# cereal-sch.net
KiCad netlist of a schematic drawn in Altium Designer
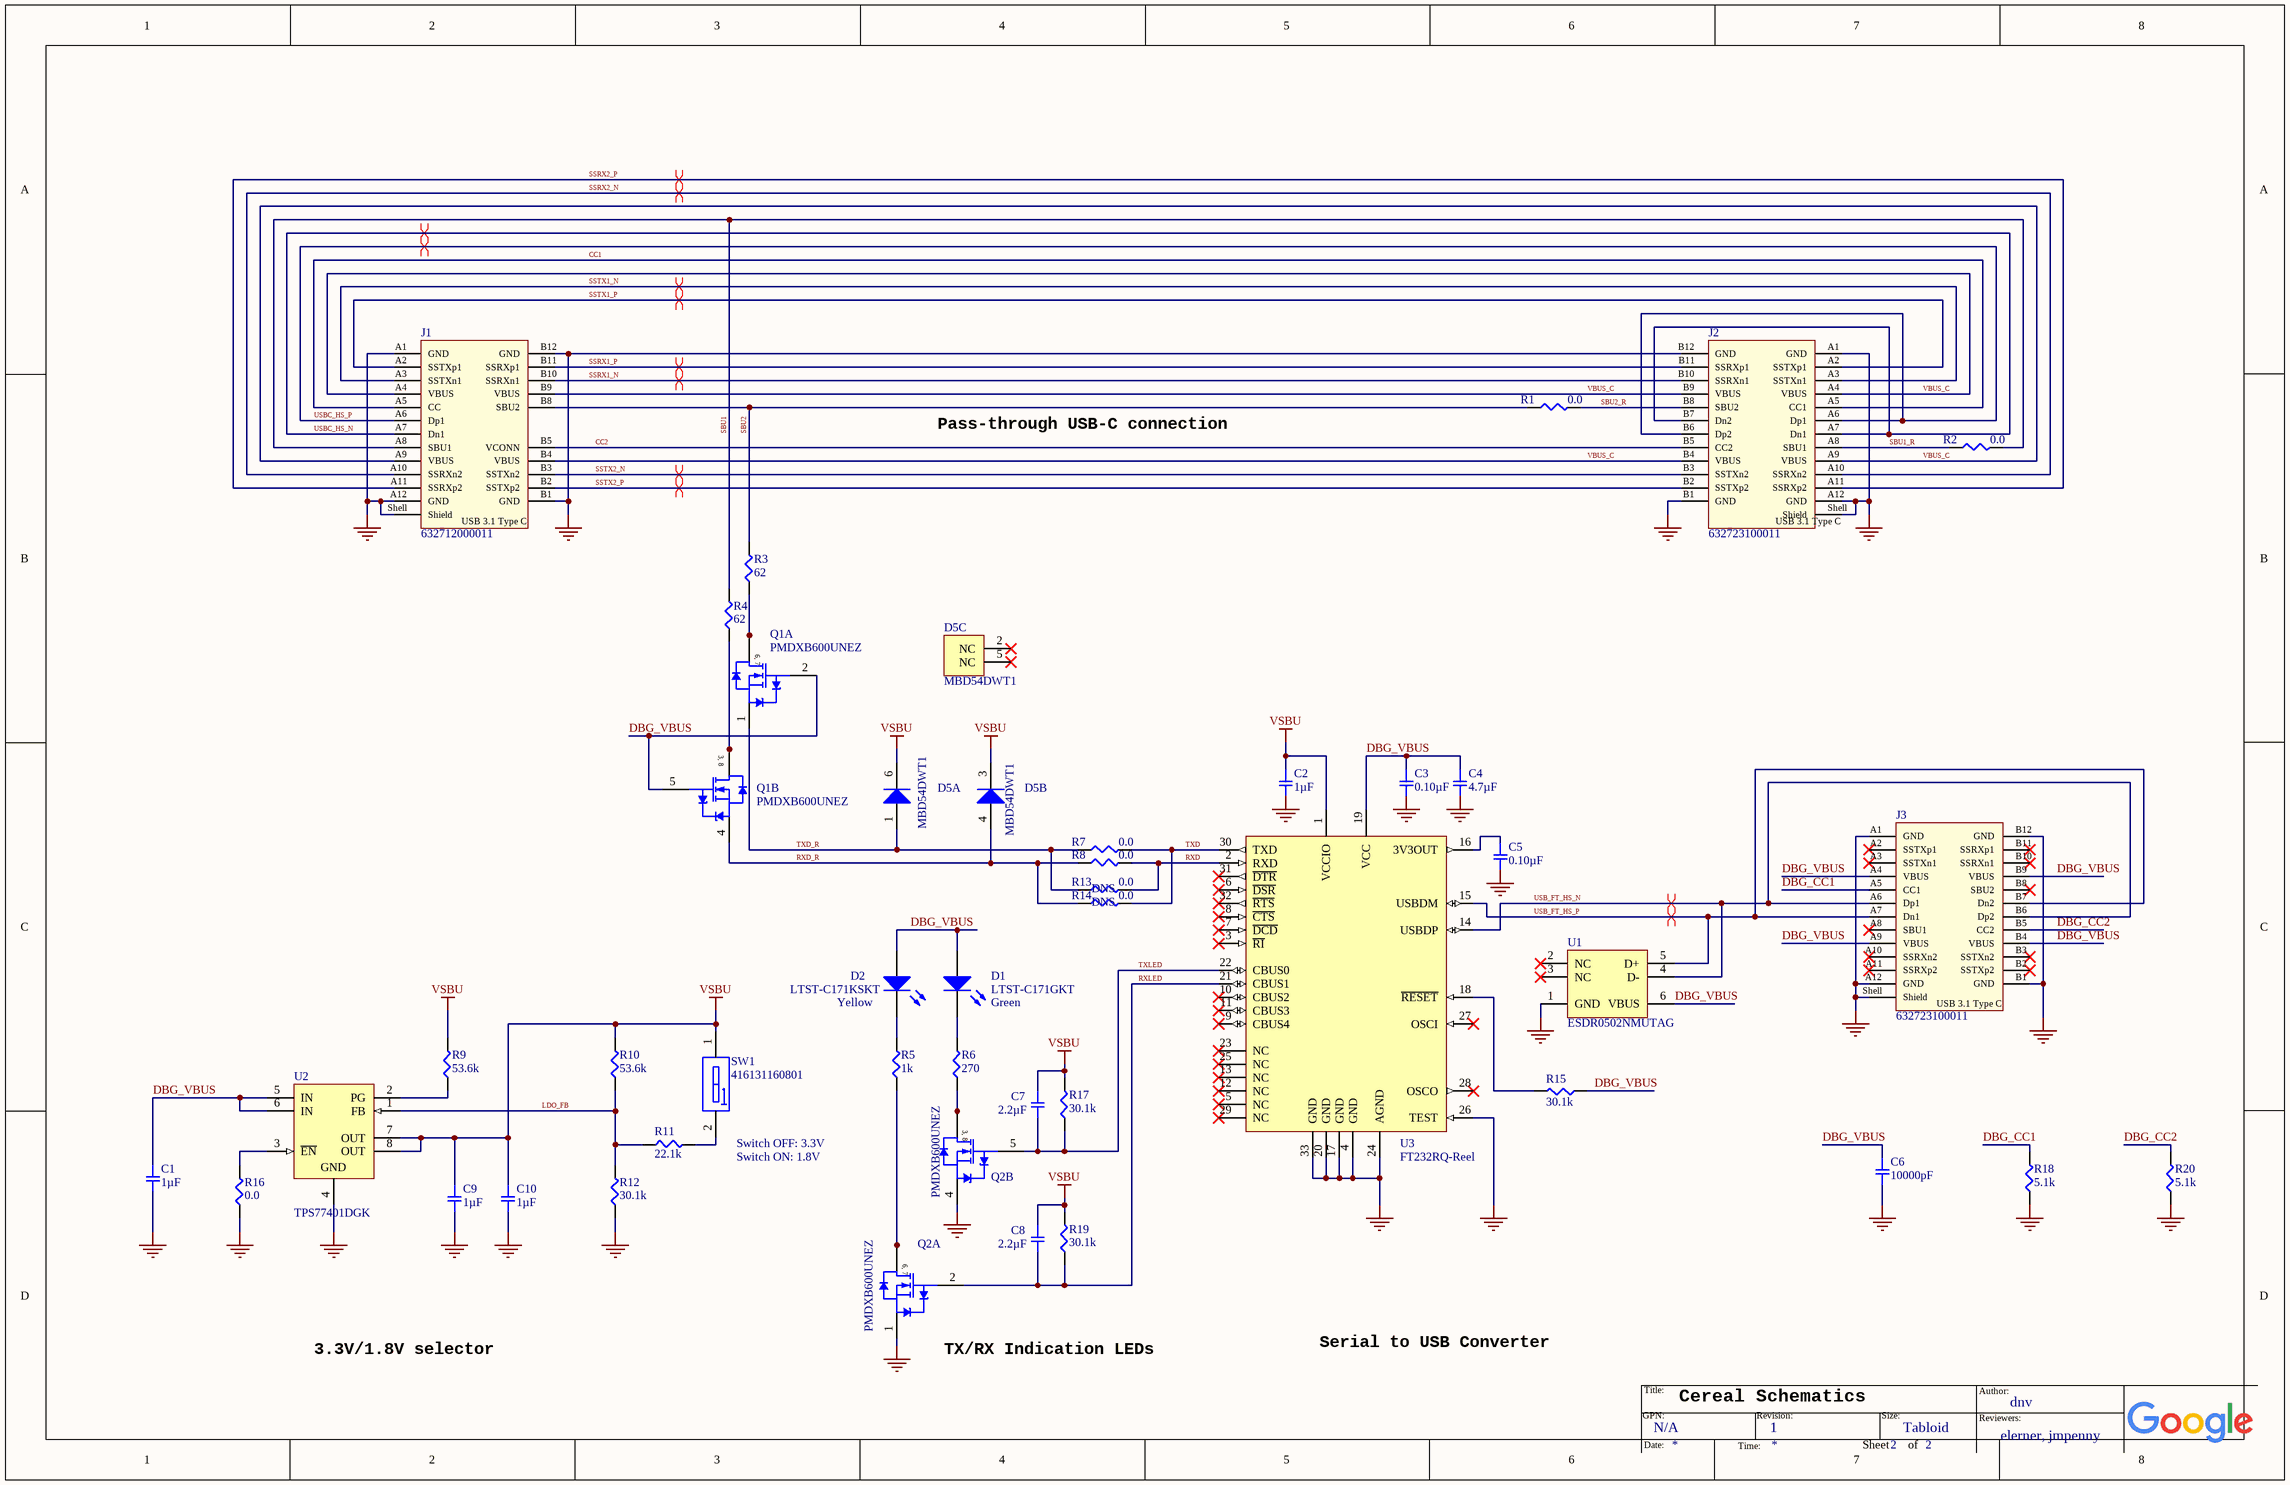
[diagram p0: cereal-sch.SchDoc]

(export (version "E")
  (design (tool "Eeschema 10.0.6"))
  (components
    (comp (ref "C1")
      (value "1µF")
      (footprint "SMD-0201C")
      (description "CAP CER 1UF 6.3V X5R 0201")
      (fields
        (field (name "DIGI-KEY PART NUMBER") "490-7229-1-ND")
        (field (name "PART NUMBER") "GRM033R60J105MEA2D")
      )
      (libsource (lib "capacitor_murata_0201") (part "GRM033R60J105MEA2D"))
    )
    (comp (ref "C2")
      (value "1µF")
      (footprint "SMD-0201C")
      (description "CAP CER 1UF 6.3V X5R 0201")
      (fields
        (field (name "DIGI-KEY PART NUMBER") "490-7229-1-ND")
        (field (name "PART NUMBER") "GRM033R60J105MEA2D")
      )
      (libsource (lib "capacitor_murata_0201") (part "GRM033R60J105MEA2D"))
    )
    (comp (ref "C3")
      (value "0.10µF")
      (footprint "SMD-0201C")
      (description "CAP CER 0.1UF 10V X5R 0201")
      (fields
        (field (name "DIGI-KEY PART NUMBER") "490-5881-1-ND")
        (field (name "PART NUMBER") "GRM033R61A104KE15D")
      )
      (libsource (lib "capacitor_murata_0201") (part "GRM033R61A104KE15D"))
    )
    (comp (ref "C4")
      (value "4.7µF")
      (footprint "SMD-0402C")
      (description "CAP CER 4.7UF 4V X5R 0402")
      (fields
        (field (name "DIGI-KEY PART NUMBER") "490-13231-1-ND")
        (field (name "PART NUMBER") "GRM153R60G475ME15D")
      )
      (libsource (lib "capacitor_murata_0402") (part "GRM153R60G475ME15D"))
    )
    (comp (ref "C5")
      (value "0.10µF")
      (footprint "SMD-0201C")
      (description "CAP CER 0.1UF 10V X5R 0201")
      (fields
        (field (name "DIGI-KEY PART NUMBER") "490-5881-1-ND")
        (field (name "PART NUMBER") "GRM033R61A104KE15D")
      )
      (libsource (lib "capacitor_murata_0201") (part "GRM033R61A104KE15D"))
    )
    (comp (ref "C6")
      (value "10000pF")
      (footprint "SMD-0201C")
      (description "CAP CER 10000PF 10V X5R 0201")
      (fields
        (field (name "DIGI-KEY PART NUMBER") "490-8156-1-ND")
        (field (name "PART NUMBER") "GRM033R61A103KA01J")
      )
      (libsource (lib "capacitor_murata_0201") (part "GRM033R61A103KA01J"))
    )
    (comp (ref "C7")
      (value "2.2µF")
      (footprint "SMD-0201C")
      (description "CAP CER 2.2UF 10V X5R 0201")
      (fields
        (field (name "DIGI-KEY PART NUMBER") "490-13227-1-ND")
        (field (name "PART NUMBER") "GRM033R61A225KE47D")
      )
      (libsource (lib "cap_murata_0201") (part "GRM033R61A225KE47D"))
    )
    (comp (ref "C8")
      (value "2.2µF")
      (footprint "SMD-0201C")
      (description "CAP CER 2.2UF 10V X5R 0201")
      (fields
        (field (name "DIGI-KEY PART NUMBER") "490-13227-1-ND")
        (field (name "PART NUMBER") "GRM033R61A225KE47D")
      )
      (libsource (lib "cap_murata_0201") (part "GRM033R61A225KE47D"))
    )
    (comp (ref "C9")
      (value "1µF")
      (footprint "SMD-0201C")
      (description "CAP CER 1UF 6.3V X5R 0201")
      (fields
        (field (name "DIGI-KEY PART NUMBER") "490-7229-1-ND")
        (field (name "PART NUMBER") "GRM033R60J105MEA2D")
      )
      (libsource (lib "capacitor_murata_0201") (part "GRM033R60J105MEA2D"))
    )
    (comp (ref "C10")
      (value "1µF")
      (footprint "SMD-0201C")
      (description "CAP CER 1UF 6.3V X5R 0201")
      (fields
        (field (name "DIGI-KEY PART NUMBER") "490-7229-1-ND")
        (field (name "PART NUMBER") "GRM033R60J105MEA2D")
      )
      (libsource (lib "capacitor_murata_0201") (part "GRM033R60J105MEA2D"))
    )
    (comp (ref "D1")
      (value "LTST-C171GKT")
      (footprint "0805")
      (description "LED")
      (fields (field (name "COLOR") "Green"))
      (libsource (lib "lite-on") (part "LTST-C171GKT"))
    )
    (comp (ref "D2")
      (value "LTST-C171KSKT")
      (footprint "0805")
      (description "LED")
      (fields (field (name "COLOR") "Yellow"))
      (libsource (lib "lite-on") (part "LTST-C171KSKT"))
    )
    (comp (ref "D5")
      (value "MBD54DWT1")
      (footprint "ONSC-SOT-363-6-419B-02_W_V")
      (description "Dual Schottky Barrier Diodes, 6-Pin SOT-363, Tape and Reel")
      (fields (field (name "MANUFACTURER") "On Semiconductor"))
      (libsource (lib "") (part "MBD54DWT1_1"))
    )
    (comp (ref "J1")
      (value "632712000011")
      (footprint "632712000011")
      (description "USB 3.1 Type C Plug Horizontal SMT WR-COM")
      (fields (field (name "PUBLISHER") "Wurth Elektronik"))
      (libsource (lib "connector_usbc") (part "632712000011"))
    )
    (comp (ref "J2")
      (value "632723100011")
      (footprint "632723100011")
      (description "USB 3.1 Type C Receptacle Horizontal THR WR-COM")
      (fields (field (name "PUBLISHER") "Wurth Elektronik"))
      (libsource (lib "connector_usbc") (part "632723100011"))
    )
    (comp (ref "J3")
      (value "632723100011")
      (footprint "632723100011")
      (description "USB 3.1 Type C Receptacle Horizontal THR WR-COM")
      (fields (field (name "PUBLISHER") "Wurth Elektronik"))
      (libsource (lib "") (part "632723100011_1"))
    )
    (comp (ref "Q1")
      (value "PMDXB600UNEZ")
      (footprint "NXP-SOT1216_N")
      (description "Dual N-Channel Trench MOSFET, 20 V, 0.6 A, -55 to 150 degC, 8-Pin SOT1216")
      (fields (field (name "MANUFACTURER") "NXP Semiconductors"))
      (libsource (lib "transistor_NXP_standard_MOSFETs") (part "PMDXB600UNEZ"))
    )
    (comp (ref "Q2")
      (value "PMDXB600UNEZ")
      (footprint "NXP-SOT1216_N")
      (description "Dual N-Channel Trench MOSFET, 20 V, 0.6 A, -55 to 150 degC, 8-Pin SOT1216")
      (fields (field (name "MANUFACTURER") "NXP Semiconductors"))
      (libsource (lib "transistor_NXP_standard_MOSFETs") (part "PMDXB600UNEZ"))
    )
    (comp (ref "R1")
      (value "0.0")
      (footprint "SMD-0201-RES")
      (description "RES SMD 0.0OHM JUMPER 1/20W 0201")
      (fields (field (name "PART NUMBER") "ERJ-1GN0R00C") (field (name "DIGI-KEY PART NUMBER") "P15979CT-ND"))
      (libsource (lib "resistor_0201_panasonic_ERJ") (part "ERJ-1GN0R00C"))
    )
    (comp (ref "R2")
      (value "0.0")
      (footprint "SMD-0201-RES")
      (description "RES SMD 0.0OHM JUMPER 1/20W 0201")
      (fields (field (name "PART NUMBER") "ERJ-1GN0R00C") (field (name "DIGI-KEY PART NUMBER") "P15979CT-ND"))
      (libsource (lib "resistor_0201_panasonic_ERJ") (part "ERJ-1GN0R00C"))
    )
    (comp (ref "R3")
      (value "62")
      (footprint "SMD-0402-RES")
      (description "RES SMD 62 OHM 5% 1/10W 0402")
      (fields (field (name "PART NUMBER") "ERJ-2GEJ620X") (field (name "DIGI-KEY PART NUMBER") "P62JCT-ND"))
      (libsource (lib "resisitor_0402_panasonic_ERJ") (part "ERJ-2GEJ620X"))
    )
    (comp (ref "R4")
      (value "62")
      (footprint "SMD-0402-RES")
      (description "RES SMD 62 OHM 5% 1/10W 0402")
      (fields (field (name "PART NUMBER") "ERJ-2GEJ620X") (field (name "DIGI-KEY PART NUMBER") "P62JCT-ND"))
      (libsource (lib "resisitor_0402_panasonic_ERJ") (part "ERJ-2GEJ620X"))
    )
    (comp (ref "R5")
      (value "1k")
      (footprint "SMD-0201-RES")
      (description "RES SMD 1K OHM 1% 1/20W 0201")
      (fields
        (field (name "PART NUMBER") "ERJ-1GEF1001C")
        (field (name "DIGI-KEY PART NUMBER") "P1.00KABCT-ND")
      )
      (libsource (lib "res_0201_panasonic_ERJ") (part "ERJ-1GEF1001C"))
    )
    (comp (ref "R6")
      (value "270")
      (footprint "SMD-0201-RES")
      (description "RES SMD 270 OHM 1% 1/20W 0201")
      (fields
        (field (name "PART NUMBER") "ERJ-1GEF2700C")
        (field (name "DIGI-KEY PART NUMBER") "P270ABCT-ND")
      )
      (libsource (lib "resistor_0201_panasonic_ERJ") (part "ERJ-1GEF2700C"))
    )
    (comp (ref "R7")
      (value "0.0")
      (footprint "SMD-0201-RES")
      (description "RES SMD 0.0OHM JUMPER 1/20W 0201")
      (fields (field (name "PART NUMBER") "ERJ-1GN0R00C") (field (name "DIGI-KEY PART NUMBER") "P15979CT-ND"))
      (libsource (lib "resistor_0201_panasonic_ERJ") (part "ERJ-1GN0R00C"))
    )
    (comp (ref "R8")
      (value "0.0")
      (footprint "SMD-0201-RES")
      (description "RES SMD 0.0OHM JUMPER 1/20W 0201")
      (fields (field (name "PART NUMBER") "ERJ-1GN0R00C") (field (name "DIGI-KEY PART NUMBER") "P15979CT-ND"))
      (libsource (lib "resistor_0201_panasonic_ERJ") (part "ERJ-1GN0R00C"))
    )
    (comp (ref "R9")
      (value "53.6k")
      (footprint "SMD-0201-RES")
      (description "RES SMD 53.6K OHM 1% 1/20W 0201")
      (fields
        (field (name "PART NUMBER") "ERJ-1GEF5362C")
        (field (name "DIGI-KEY PART NUMBER") "P53.6KABCT-ND")
      )
      (libsource (lib "resistor_0201_panasonic_ERJ") (part "ERJ-1GEF5362C"))
    )
    (comp (ref "R10")
      (value "53.6k")
      (footprint "SMD-0201-RES")
      (description "RES SMD 53.6K OHM 1% 1/20W 0201")
      (fields
        (field (name "PART NUMBER") "ERJ-1GEF5362C")
        (field (name "DIGI-KEY PART NUMBER") "P53.6KABCT-ND")
      )
      (libsource (lib "resistor_0201_panasonic_ERJ") (part "ERJ-1GEF5362C"))
    )
    (comp (ref "R11")
      (value "22.1k")
      (footprint "SMD-0201-RES")
      (description "RES SMD 22.1K OHM 1% 1/20W 0201")
      (fields
        (field (name "PART NUMBER") "ERJ-1GEF2212C")
        (field (name "DIGI-KEY PART NUMBER") "P22.1KABCT-ND")
      )
      (libsource (lib "resistor_0201_panasonic_ERJ") (part "ERJ-1GEF2212C"))
    )
    (comp (ref "R12")
      (value "30.1k")
      (footprint "SMD-0201-RES")
      (description "RES SMD 30.1K OHM 1% 1/20W 0201")
      (fields
        (field (name "PART NUMBER") "ERJ-1GEF3012C")
        (field (name "DIGI-KEY PART NUMBER") "P30.1KABCT-ND")
      )
      (libsource (lib "resistor_0201_panasonic_ERJ") (part "ERJ-1GEF3012C"))
    )
    (comp (ref "R13")
      (value "0.0")
      (footprint "SMD-0201-RES")
      (description "RES SMD 0.0OHM JUMPER 1/20W 0201")
      (fields
        (field (name "PART NUMBER") "ERJ-1GN0R00C")
        (field (name "DIGI-KEY PART NUMBER") "P15979CT-ND")
        (field (name "POPULATE") "DNS")
      )
      (libsource (lib "resistor_0201_panasonic_ERJ") (part "ERJ-1GN0R00C"))
    )
    (comp (ref "R14")
      (value "0.0")
      (footprint "SMD-0201-RES")
      (description "RES SMD 0.0OHM JUMPER 1/20W 0201")
      (fields
        (field (name "PART NUMBER") "ERJ-1GN0R00C")
        (field (name "DIGI-KEY PART NUMBER") "P15979CT-ND")
        (field (name "POPULATE") "DNS")
      )
      (libsource (lib "resistor_0201_panasonic_ERJ") (part "ERJ-1GN0R00C"))
    )
    (comp (ref "R15")
      (value "30.1k")
      (footprint "SMD-0201-RES")
      (description "RES SMD 30.1K OHM 1% 1/20W 0201")
      (fields
        (field (name "PART NUMBER") "ERJ-1GEF3012C")
        (field (name "DIGI-KEY PART NUMBER") "P30.1KABCT-ND")
      )
      (libsource (lib "resistor_0201_panasonic_ERJ") (part "ERJ-1GEF3012C"))
    )
    (comp (ref "R16")
      (value "0.0")
      (footprint "SMD-0201-RES")
      (description "RES SMD 0.0OHM JUMPER 1/20W 0201")
      (fields (field (name "PART NUMBER") "ERJ-1GN0R00C") (field (name "DIGI-KEY PART NUMBER") "P15979CT-ND"))
      (libsource (lib "resistor_0201_panasonic_ERJ") (part "ERJ-1GN0R00C"))
    )
    (comp (ref "R17")
      (value "30.1k")
      (footprint "SMD-0201-RES")
      (description "RES SMD 30.1K OHM 1% 1/20W 0201")
      (fields
        (field (name "PART NUMBER") "ERJ-1GEF3012C")
        (field (name "DIGI-KEY PART NUMBER") "P30.1KABCT-ND")
      )
      (libsource (lib "resistor_0201_panasonic_ERJ") (part "ERJ-1GEF3012C"))
    )
    (comp (ref "R18")
      (value "5.1k")
      (footprint "SMD-0201-RES")
      (description "RES SMD 5.1K OHM 1% 1/20W 0201")
      (fields
        (field (name "PART NUMBER") "ERJ-1GEF5101C")
        (field (name "DIGI-KEY PART NUMBER") "P5.10KABCT-ND")
      )
      (libsource (lib "resistor_0201_panasonic_ERJ") (part "ERJ-1GEF5101C"))
    )
    (comp (ref "R19")
      (value "30.1k")
      (footprint "SMD-0201-RES")
      (description "RES SMD 30.1K OHM 1% 1/20W 0201")
      (fields
        (field (name "PART NUMBER") "ERJ-1GEF3012C")
        (field (name "DIGI-KEY PART NUMBER") "P30.1KABCT-ND")
      )
      (libsource (lib "resistor_0201_panasonic_ERJ") (part "ERJ-1GEF3012C"))
    )
    (comp (ref "R20")
      (value "5.1k")
      (footprint "SMD-0201-RES")
      (description "RES SMD 5.1K OHM 1% 1/20W 0201")
      (fields
        (field (name "PART NUMBER") "ERJ-1GEF5101C")
        (field (name "DIGI-KEY PART NUMBER") "P5.10KABCT-ND")
      )
      (libsource (lib "resistor_0201_panasonic_ERJ") (part "ERJ-1GEF5101C"))
    )
    (comp (ref "SW1")
      (value "416131160801")
      (footprint "416131160801")
      (description "WS-DISV 1.27 mm small compact SMD Dip Switch with top tape")
      (libsource (lib "WS-DISV 1.27 mm small compact SMD Dip Switch with top tape") (part "416131160801"))
    )
    (comp (ref "U1")
      (value "ESDR0502NMUTAG")
      (footprint "ONSC-UDFN-6-517AA-01_V")
      (fields (field (name "MANUFACTURER") "On Semiconductor"))
      (libsource (lib "diode_esd_ON_Semi") (part "ESDR0502NMUTAG"))
    )
    (comp (ref "U2")
      (value "TPS77401DGK")
      (footprint "TI-DGK8_N")
      (fields (field (name "MANUFACTURER") "Texas Instruments"))
      (libsource (lib "ic_pwr_ldo_TI_single_channel_ldo_0-350mA") (part "TPS77401DGK"))
    )
    (comp (ref "U3")
      (value "FT232RQ-Reel")
      (footprint "PQFN5X5-32_V")
      (description "USB UART Asynchronous Serial Data Transfer Chip, 32-pin QFN, Tape and Reel")
      (fields (field (name "MANUFACTURER") "FTDI"))
      (libsource (lib "ic_interface_FTDI") (part "FT232RQ-Reel"))
    )
  )
  (nets
    (net (code "1") (name "/CC1") (class "Default")
      (node (ref "J1") (pin "A5") (pinfunction "CC_A5") (pintype "passive"))
      (node (ref "J2") (pin "A5") (pinfunction "CC1_A5") (pintype "passive"))
    )
    (net (code "2") (name "/CC2") (class "Default")
      (node (ref "J1") (pin "B5") (pinfunction "VCONN_B5") (pintype "passive"))
      (node (ref "J2") (pin "B5") (pinfunction "CC2_B5") (pintype "passive"))
    )
    (net (code "3") (name "/DBG_CC1") (class "Default")
      (node (ref "J3") (pin "A5") (pinfunction "CC1_A5") (pintype "passive"))
      (node (ref "R18") (pin "2") (pinfunction "2_2") (pintype "passive"))
    )
    (net (code "4") (name "/DBG_CC2") (class "Default")
      (node (ref "J3") (pin "B5") (pinfunction "CC2_B5") (pintype "passive"))
      (node (ref "R20") (pin "2") (pinfunction "2_2") (pintype "passive"))
    )
    (net (code "5") (name "/DBG_VBUS") (class "Default")
      (node (ref "C1") (pin "1") (pinfunction "1_1") (pintype "passive"))
      (node (ref "C3") (pin "1") (pinfunction "1_1") (pintype "passive"))
      (node (ref "C4") (pin "1") (pinfunction "1_1") (pintype "passive"))
      (node (ref "C6") (pin "1") (pinfunction "1_1") (pintype "passive"))
      (node (ref "D1") (pin "1") (pinfunction "A_1") (pintype "passive"))
      (node (ref "D2") (pin "1") (pinfunction "A_1") (pintype "passive"))
      (node (ref "J3") (pin "A4") (pinfunction "VBUS_A4") (pintype "passive"))
      (node (ref "J3") (pin "A9") (pinfunction "VBUS_A9") (pintype "passive"))
      (node (ref "J3") (pin "B4") (pinfunction "VBUS_B4") (pintype "passive"))
      (node (ref "J3") (pin "B9") (pinfunction "VBUS_B9") (pintype "passive"))
      (node (ref "Q1") (pin "2") (pinfunction "G1_2") (pintype "passive"))
      (node (ref "Q1") (pin "5") (pinfunction "G2_5") (pintype "passive"))
      (node (ref "R15") (pin "1") (pinfunction "1_1") (pintype "passive"))
      (node (ref "U1") (pin "6") (pinfunction "VBUS_6") (pintype "power_in"))
      (node (ref "U2") (pin "5") (pinfunction "IN_5") (pintype "power_in"))
      (node (ref "U2") (pin "6") (pinfunction "IN_6") (pintype "power_in"))
      (node (ref "U3") (pin "19") (pinfunction "VCC_19") (pintype "power_in"))
    )
    (net (code "6") (name "/LDO_FB") (class "Default")
      (node (ref "R10") (pin "1") (pinfunction "1_1") (pintype "passive"))
      (node (ref "R11") (pin "1") (pinfunction "1_1") (pintype "passive"))
      (node (ref "R12") (pin "2") (pinfunction "2_2") (pintype "passive"))
      (node (ref "U2") (pin "1") (pinfunction "FB_1") (pintype "input"))
    )
    (net (code "7") (name "/RXD") (class "Default")
      (node (ref "R13") (pin "2") (pinfunction "2_2") (pintype "passive"))
      (node (ref "R8") (pin "2") (pinfunction "2_2") (pintype "passive"))
      (node (ref "U3") (pin "2") (pinfunction "RXD_2") (pintype "input"))
    )
    (net (code "8") (name "/RXD_R") (class "Default")
      (node (ref "D5") (pin "4") (pinfunction "A1_4") (pintype "passive"))
      (node (ref "Q1") (pin "4") (pinfunction "S2_4") (pintype "passive"))
      (node (ref "R14") (pin "1") (pinfunction "1_1") (pintype "passive"))
      (node (ref "R8") (pin "1") (pinfunction "1_1") (pintype "passive"))
    )
    (net (code "9") (name "/RXLED") (class "Default")
      (node (ref "C8") (pin "2") (pinfunction "2_2") (pintype "passive"))
      (node (ref "Q2") (pin "2") (pinfunction "G1_2") (pintype "passive"))
      (node (ref "R19") (pin "1") (pinfunction "1_1") (pintype "passive"))
      (node (ref "U3") (pin "21") (pinfunction "CBUS1_21") (pintype "bidirectional"))
    )
    (net (code "10") (name "/SBU1") (class "Default")
      (node (ref "J1") (pin "A8") (pinfunction "SBU1_A8") (pintype "passive"))
      (node (ref "R2") (pin "2") (pinfunction "2_2") (pintype "passive"))
      (node (ref "R4") (pin "2") (pinfunction "2_2") (pintype "passive"))
    )
    (net (code "11") (name "/SBU1_R") (class "Default")
      (node (ref "J2") (pin "A8") (pinfunction "SBU1_A8") (pintype "passive"))
      (node (ref "R2") (pin "1") (pinfunction "1_1") (pintype "passive"))
    )
    (net (code "12") (name "/SBU2") (class "Default")
      (node (ref "J1") (pin "B8") (pinfunction "SBU2_B8") (pintype "passive"))
      (node (ref "R1") (pin "1") (pinfunction "1_1") (pintype "passive"))
      (node (ref "R3") (pin "2") (pinfunction "2_2") (pintype "passive"))
    )
    (net (code "13") (name "/SBU2_R") (class "Default")
      (node (ref "J2") (pin "B8") (pinfunction "SBU2_B8") (pintype "passive"))
      (node (ref "R1") (pin "2") (pinfunction "2_2") (pintype "passive"))
    )
    (net (code "14") (name "/SSRX1_N") (class "Default")
      (node (ref "J1") (pin "B10") (pinfunction "SSRXn1_B10") (pintype "passive"))
      (node (ref "J2") (pin "B10") (pinfunction "SSRXn1_B10") (pintype "passive"))
    )
    (net (code "15") (name "/SSRX1_P") (class "Default")
      (node (ref "J1") (pin "B11") (pinfunction "SSRXp1_B11") (pintype "passive"))
      (node (ref "J2") (pin "B11") (pinfunction "SSRXp1_B11") (pintype "passive"))
    )
    (net (code "16") (name "/SSRX2_N") (class "Default")
      (node (ref "J1") (pin "A10") (pinfunction "SSRXn2_A10") (pintype "passive"))
      (node (ref "J2") (pin "A10") (pinfunction "SSRXn2_A10") (pintype "passive"))
    )
    (net (code "17") (name "/SSRX2_P") (class "Default")
      (node (ref "J1") (pin "A11") (pinfunction "SSRXp2_A11") (pintype "passive"))
      (node (ref "J2") (pin "A11") (pinfunction "SSRXp2_A11") (pintype "passive"))
    )
    (net (code "18") (name "/SSTX1_N") (class "Default")
      (node (ref "J1") (pin "A3") (pinfunction "SSTXn1_A3") (pintype "passive"))
      (node (ref "J2") (pin "A3") (pinfunction "SSTXn1_A3") (pintype "passive"))
    )
    (net (code "19") (name "/SSTX1_P") (class "Default")
      (node (ref "J1") (pin "A2") (pinfunction "SSTXp1_A2") (pintype "passive"))
      (node (ref "J2") (pin "A2") (pinfunction "SSTXp1_A2") (pintype "passive"))
    )
    (net (code "20") (name "/SSTX2_N") (class "Default")
      (node (ref "J1") (pin "B3") (pinfunction "SSTXn2_B3") (pintype "passive"))
      (node (ref "J2") (pin "B3") (pinfunction "SSTXn2_B3") (pintype "passive"))
    )
    (net (code "21") (name "/SSTX2_P") (class "Default")
      (node (ref "J1") (pin "B2") (pinfunction "SSTXp2_B2") (pintype "passive"))
      (node (ref "J2") (pin "B2") (pinfunction "SSTXp2_B2") (pintype "passive"))
    )
    (net (code "22") (name "/TXD") (class "Default")
      (node (ref "R14") (pin "2") (pinfunction "2_2") (pintype "passive"))
      (node (ref "R7") (pin "2") (pinfunction "2_2") (pintype "passive"))
      (node (ref "U3") (pin "30") (pinfunction "TXD_30") (pintype "output"))
    )
    (net (code "23") (name "/TXD_R") (class "Default")
      (node (ref "D5") (pin "1") (pinfunction "A2_1") (pintype "passive"))
      (node (ref "Q1") (pin "1") (pinfunction "S1_1") (pintype "passive"))
      (node (ref "R13") (pin "1") (pinfunction "1_1") (pintype "passive"))
      (node (ref "R7") (pin "1") (pinfunction "1_1") (pintype "passive"))
    )
    (net (code "24") (name "/TXLED") (class "Default")
      (node (ref "C7") (pin "2") (pinfunction "2_2") (pintype "passive"))
      (node (ref "Q2") (pin "5") (pinfunction "G2_5") (pintype "passive"))
      (node (ref "R17") (pin "1") (pinfunction "1_1") (pintype "passive"))
      (node (ref "U3") (pin "22") (pinfunction "CBUS0_22") (pintype "bidirectional"))
    )
    (net (code "25") (name "/USBC_HS_N") (class "Default")
      (node (ref "J1") (pin "A7") (pinfunction "Dn1_A7") (pintype "passive"))
      (node (ref "J2") (pin "A7") (pinfunction "Dn1_A7") (pintype "passive"))
      (node (ref "J2") (pin "B7") (pinfunction "Dn2_B7") (pintype "passive"))
    )
    (net (code "26") (name "/USBC_HS_P") (class "Default")
      (node (ref "J1") (pin "A6") (pinfunction "Dp1_A6") (pintype "passive"))
      (node (ref "J2") (pin "A6") (pinfunction "Dp1_A6") (pintype "passive"))
      (node (ref "J2") (pin "B6") (pinfunction "Dp2_B6") (pintype "passive"))
    )
    (net (code "27") (name "/USB_FT_HS_N") (class "Default")
      (node (ref "J3") (pin "A6") (pinfunction "Dp1_A6") (pintype "passive"))
      (node (ref "J3") (pin "B6") (pinfunction "Dp2_B6") (pintype "passive"))
      (node (ref "U1") (pin "4") (pinfunction "D-_4") (pintype "passive"))
      (node (ref "U3") (pin "14") (pinfunction "USBDP_14") (pintype "bidirectional"))
    )
    (net (code "28") (name "/USB_FT_HS_P") (class "Default")
      (node (ref "J3") (pin "A7") (pinfunction "Dn1_A7") (pintype "passive"))
      (node (ref "J3") (pin "B7") (pinfunction "Dn2_B7") (pintype "passive"))
      (node (ref "U1") (pin "5") (pinfunction "D+_5") (pintype "passive"))
      (node (ref "U3") (pin "15") (pinfunction "USBDM_15") (pintype "bidirectional"))
    )
    (net (code "29") (name "/VBUS_C") (class "Default")
      (node (ref "J1") (pin "A4") (pinfunction "VBUS_A4") (pintype "passive"))
      (node (ref "J1") (pin "A9") (pinfunction "VBUS_A9") (pintype "passive"))
      (node (ref "J1") (pin "B4") (pinfunction "VBUS_B4") (pintype "passive"))
      (node (ref "J1") (pin "B9") (pinfunction "VBUS_B9") (pintype "passive"))
      (node (ref "J2") (pin "A4") (pinfunction "VBUS_A4") (pintype "passive"))
      (node (ref "J2") (pin "A9") (pinfunction "VBUS_A9") (pintype "passive"))
      (node (ref "J2") (pin "B4") (pinfunction "VBUS_B4") (pintype "passive"))
      (node (ref "J2") (pin "B9") (pinfunction "VBUS_B9") (pintype "passive"))
    )
    (net (code "30") (name "GND") (class "Default")
      (node (ref "C1") (pin "2") (pinfunction "2_2") (pintype "passive"))
      (node (ref "C10") (pin "2") (pinfunction "2_2") (pintype "passive"))
      (node (ref "C2") (pin "2") (pinfunction "2_2") (pintype "passive"))
      (node (ref "C3") (pin "2") (pinfunction "2_2") (pintype "passive"))
      (node (ref "C4") (pin "2") (pinfunction "2_2") (pintype "passive"))
      (node (ref "C5") (pin "2") (pinfunction "2_2") (pintype "passive"))
      (node (ref "C6") (pin "2") (pinfunction "2_2") (pintype "passive"))
      (node (ref "C9") (pin "2") (pinfunction "2_2") (pintype "passive"))
      (node (ref "J1") (pin "A1") (pinfunction "GND_A1") (pintype "passive"))
      (node (ref "J1") (pin "A12") (pinfunction "GND_A12") (pintype "passive"))
      (node (ref "J1") (pin "B1") (pinfunction "GND_B1") (pintype "passive"))
      (node (ref "J1") (pin "B12") (pinfunction "GND_B12") (pintype "passive"))
      (node (ref "J1") (pin "Shell") (pinfunction "Shield_Shell") (pintype "passive"))
      (node (ref "J2") (pin "A1") (pinfunction "GND_A1") (pintype "passive"))
      (node (ref "J2") (pin "A12") (pinfunction "GND_A12") (pintype "passive"))
      (node (ref "J2") (pin "B1") (pinfunction "GND_B1") (pintype "passive"))
      (node (ref "J2") (pin "B12") (pinfunction "GND_B12") (pintype "passive"))
      (node (ref "J2") (pin "Shell") (pinfunction "Shield_Shell") (pintype "passive"))
      (node (ref "J3") (pin "A1") (pinfunction "GND_A1") (pintype "passive"))
      (node (ref "J3") (pin "A12") (pinfunction "GND_A12") (pintype "passive"))
      (node (ref "J3") (pin "B1") (pinfunction "GND_B1") (pintype "passive"))
      (node (ref "J3") (pin "B12") (pinfunction "GND_B12") (pintype "passive"))
      (node (ref "J3") (pin "Shell") (pinfunction "Shield_Shell") (pintype "passive"))
      (node (ref "Q2") (pin "1") (pinfunction "S1_1") (pintype "passive"))
      (node (ref "Q2") (pin "4") (pinfunction "S2_4") (pintype "passive"))
      (node (ref "R12") (pin "1") (pinfunction "1_1") (pintype "passive"))
      (node (ref "R16") (pin "1") (pinfunction "1_1") (pintype "passive"))
      (node (ref "R18") (pin "1") (pinfunction "1_1") (pintype "passive"))
      (node (ref "R20") (pin "1") (pinfunction "1_1") (pintype "passive"))
      (node (ref "U1") (pin "1") (pinfunction "GND_1") (pintype "power_in"))
      (node (ref "U2") (pin "4") (pinfunction "GND_4") (pintype "power_in"))
      (node (ref "U3") (pin "17") (pinfunction "GND_17") (pintype "power_in"))
      (node (ref "U3") (pin "20") (pinfunction "GND_20") (pintype "power_in"))
      (node (ref "U3") (pin "24") (pinfunction "AGND_24") (pintype "power_in"))
      (node (ref "U3") (pin "26") (pinfunction "TEST_26") (pintype "input"))
      (node (ref "U3") (pin "33") (pinfunction "GND_33") (pintype "power_in"))
      (node (ref "U3") (pin "4") (pinfunction "GND_4") (pintype "power_in"))
    )
    (net (code "31") (name "Net-(D1-K)") (class "Default")
      (node (ref "D1") (pin "2") (pinfunction "K_2") (pintype "passive"))
      (node (ref "R6") (pin "2") (pinfunction "2_2") (pintype "passive"))
    )
    (net (code "32") (name "Net-(D2-K)") (class "Default")
      (node (ref "D2") (pin "2") (pinfunction "K_2") (pintype "passive"))
      (node (ref "R5") (pin "2") (pinfunction "2_2") (pintype "passive"))
    )
    (net (code "33") (name "Net-(Q1A-D1-Pad6)") (class "Default")
      (node (ref "Q1") (pin "6") (pinfunction "D1_6") (pintype "passive"))
      (node (ref "Q1") (pin "7") (pinfunction "D1_7") (pintype "passive"))
      (node (ref "R3") (pin "1") (pinfunction "1_1") (pintype "passive"))
    )
    (net (code "34") (name "Net-(Q1B-D2-Pad3)") (class "Default")
      (node (ref "Q1") (pin "3") (pinfunction "D2_3") (pintype "passive"))
      (node (ref "Q1") (pin "8") (pinfunction "D2_8") (pintype "passive"))
      (node (ref "R4") (pin "1") (pinfunction "1_1") (pintype "passive"))
    )
    (net (code "35") (name "Net-(Q2A-D1-Pad6)") (class "Default")
      (node (ref "Q2") (pin "6") (pinfunction "D1_6") (pintype "passive"))
      (node (ref "Q2") (pin "7") (pinfunction "D1_7") (pintype "passive"))
      (node (ref "R5") (pin "1") (pinfunction "1_1") (pintype "passive"))
    )
    (net (code "36") (name "Net-(Q2B-D2-Pad3)") (class "Default")
      (node (ref "Q2") (pin "3") (pinfunction "D2_3") (pintype "passive"))
      (node (ref "Q2") (pin "8") (pinfunction "D2_8") (pintype "passive"))
      (node (ref "R6") (pin "1") (pinfunction "1_1") (pintype "passive"))
    )
    (net (code "37") (name "Net-(R11-Pad2)") (class "Default")
      (node (ref "R11") (pin "2") (pinfunction "2_2") (pintype "passive"))
      (node (ref "SW1") (pin "2") (pinfunction "2_2") (pintype "passive"))
    )
    (net (code "38") (name "Net-(U2-PG)") (class "Default")
      (node (ref "R9") (pin "1") (pinfunction "1_1") (pintype "passive"))
      (node (ref "U2") (pin "2") (pinfunction "PG_2") (pintype "tri_state"))
    )
    (net (code "39") (name "Net-(U2-~{EN})") (class "Default")
      (node (ref "R16") (pin "2") (pinfunction "2_2") (pintype "passive"))
      (node (ref "U2") (pin "3") (pinfunction "~{EN}_3") (pintype "input"))
    )
    (net (code "40") (name "Net-(U3-3V3OUT)") (class "Default")
      (node (ref "C5") (pin "1") (pinfunction "1_1") (pintype "passive"))
      (node (ref "U3") (pin "16") (pinfunction "3V3OUT_16") (pintype "output"))
    )
    (net (code "41") (name "Net-(U3-~{RESET})") (class "Default")
      (node (ref "R15") (pin "2") (pinfunction "2_2") (pintype "passive"))
      (node (ref "U3") (pin "18") (pinfunction "~{RESET}_18") (pintype "input"))
    )
    (net (code "42") (name "VSBU") (class "Default")
      (node (ref "C10") (pin "1") (pinfunction "1_1") (pintype "passive"))
      (node (ref "C2") (pin "1") (pinfunction "1_1") (pintype "passive"))
      (node (ref "C7") (pin "1") (pinfunction "1_1") (pintype "passive"))
      (node (ref "C8") (pin "1") (pinfunction "1_1") (pintype "passive"))
      (node (ref "C9") (pin "1") (pinfunction "1_1") (pintype "passive"))
      (node (ref "D5") (pin "3") (pinfunction "K1_3") (pintype "passive"))
      (node (ref "D5") (pin "6") (pinfunction "K2_6") (pintype "passive"))
      (node (ref "R10") (pin "2") (pinfunction "2_2") (pintype "passive"))
      (node (ref "R17") (pin "2") (pinfunction "2_2") (pintype "passive"))
      (node (ref "R19") (pin "2") (pinfunction "2_2") (pintype "passive"))
      (node (ref "R9") (pin "2") (pinfunction "2_2") (pintype "passive"))
      (node (ref "SW1") (pin "1") (pinfunction "1_1") (pintype "passive"))
      (node (ref "U2") (pin "7") (pinfunction "OUT_7") (pintype "power_in"))
      (node (ref "U2") (pin "8") (pinfunction "OUT_8") (pintype "power_in"))
      (node (ref "U3") (pin "1") (pinfunction "VCCIO_1") (pintype "power_in"))
    )
    (net (code "43") (name "unconnected-(D5C-NC-Pad2)") (class "Default")
      (node (ref "D5") (pin "2") (pinfunction "NC_2") (pintype "passive+no_connect"))
    )
    (net (code "44") (name "unconnected-(D5C-NC-Pad5)") (class "Default")
      (node (ref "D5") (pin "5") (pinfunction "NC_5") (pintype "passive+no_connect"))
    )
    (net (code "45") (name "unconnected-(J3-SBU1-PadA8)") (class "Default")
      (node (ref "J3") (pin "A8") (pinfunction "SBU1_A8") (pintype "passive+no_connect"))
    )
    (net (code "46") (name "unconnected-(J3-SBU2-PadB8)") (class "Default")
      (node (ref "J3") (pin "B8") (pinfunction "SBU2_B8") (pintype "passive+no_connect"))
    )
    (net (code "47") (name "unconnected-(J3-SSRXn1-PadB10)") (class "Default")
      (node (ref "J3") (pin "B10") (pinfunction "SSRXn1_B10") (pintype "passive+no_connect"))
    )
    (net (code "48") (name "unconnected-(J3-SSRXn2-PadA10)") (class "Default")
      (node (ref "J3") (pin "A10") (pinfunction "SSRXn2_A10") (pintype "passive+no_connect"))
    )
    (net (code "49") (name "unconnected-(J3-SSRXp1-PadB11)") (class "Default")
      (node (ref "J3") (pin "B11") (pinfunction "SSRXp1_B11") (pintype "passive+no_connect"))
    )
    (net (code "50") (name "unconnected-(J3-SSRXp2-PadA11)") (class "Default")
      (node (ref "J3") (pin "A11") (pinfunction "SSRXp2_A11") (pintype "passive+no_connect"))
    )
    (net (code "51") (name "unconnected-(J3-SSTXn1-PadA3)") (class "Default")
      (node (ref "J3") (pin "A3") (pinfunction "SSTXn1_A3") (pintype "passive+no_connect"))
    )
    (net (code "52") (name "unconnected-(J3-SSTXn2-PadB3)") (class "Default")
      (node (ref "J3") (pin "B3") (pinfunction "SSTXn2_B3") (pintype "passive+no_connect"))
    )
    (net (code "53") (name "unconnected-(J3-SSTXp1-PadA2)") (class "Default")
      (node (ref "J3") (pin "A2") (pinfunction "SSTXp1_A2") (pintype "passive+no_connect"))
    )
    (net (code "54") (name "unconnected-(J3-SSTXp2-PadB2)") (class "Default")
      (node (ref "J3") (pin "B2") (pinfunction "SSTXp2_B2") (pintype "passive+no_connect"))
    )
    (net (code "55") (name "unconnected-(U1-NC-Pad2)") (class "Default")
      (node (ref "U1") (pin "2") (pinfunction "NC_2") (pintype "passive+no_connect"))
    )
    (net (code "56") (name "unconnected-(U1-NC-Pad3)") (class "Default")
      (node (ref "U1") (pin "3") (pinfunction "NC_3") (pintype "passive+no_connect"))
    )
    (net (code "57") (name "unconnected-(U3-CBUS2-Pad10)") (class "Default")
      (node (ref "U3") (pin "10") (pinfunction "CBUS2_10") (pintype "bidirectional+no_connect"))
    )
    (net (code "58") (name "unconnected-(U3-CBUS3-Pad11)") (class "Default")
      (node (ref "U3") (pin "11") (pinfunction "CBUS3_11") (pintype "bidirectional+no_connect"))
    )
    (net (code "59") (name "unconnected-(U3-CBUS4-Pad9)") (class "Default")
      (node (ref "U3") (pin "9") (pinfunction "CBUS4_9") (pintype "bidirectional+no_connect"))
    )
    (net (code "60") (name "unconnected-(U3-NC-Pad5)") (class "Default")
      (node (ref "U3") (pin "5") (pinfunction "NC_5") (pintype "passive+no_connect"))
    )
    (net (code "61") (name "unconnected-(U3-NC-Pad12)") (class "Default")
      (node (ref "U3") (pin "12") (pinfunction "NC_12") (pintype "passive+no_connect"))
    )
    (net (code "62") (name "unconnected-(U3-NC-Pad13)") (class "Default")
      (node (ref "U3") (pin "13") (pinfunction "NC_13") (pintype "passive+no_connect"))
    )
    (net (code "63") (name "unconnected-(U3-NC-Pad23)") (class "Default")
      (node (ref "U3") (pin "23") (pinfunction "NC_23") (pintype "passive+no_connect"))
    )
    (net (code "64") (name "unconnected-(U3-NC-Pad25)") (class "Default")
      (node (ref "U3") (pin "25") (pinfunction "NC_25") (pintype "passive+no_connect"))
    )
    (net (code "65") (name "unconnected-(U3-NC-Pad29)") (class "Default")
      (node (ref "U3") (pin "29") (pinfunction "NC_29") (pintype "passive+no_connect"))
    )
    (net (code "66") (name "unconnected-(U3-OSCI-Pad27)") (class "Default")
      (node (ref "U3") (pin "27") (pinfunction "OSCI_27") (pintype "input+no_connect"))
    )
    (net (code "67") (name "unconnected-(U3-OSCO-Pad28)") (class "Default")
      (node (ref "U3") (pin "28") (pinfunction "OSCO_28") (pintype "output+no_connect"))
    )
    (net (code "68") (name "unconnected-(U3-~{CTS}-Pad8)") (class "Default")
      (node (ref "U3") (pin "8") (pinfunction "~{CTS}_8") (pintype "input+no_connect"))
    )
    (net (code "69") (name "unconnected-(U3-~{DCD}-Pad7)") (class "Default")
      (node (ref "U3") (pin "7") (pinfunction "~{DCD}_7") (pintype "input+no_connect"))
    )
    (net (code "70") (name "unconnected-(U3-~{DSR}-Pad6)") (class "Default")
      (node (ref "U3") (pin "6") (pinfunction "~{DSR}_6") (pintype "input+no_connect"))
    )
    (net (code "71") (name "unconnected-(U3-~{DTR}-Pad31)") (class "Default")
      (node (ref "U3") (pin "31") (pinfunction "~{DTR}_31") (pintype "output+no_connect"))
    )
    (net (code "72") (name "unconnected-(U3-~{RI}-Pad3)") (class "Default")
      (node (ref "U3") (pin "3") (pinfunction "~{RI}_3") (pintype "input+no_connect"))
    )
    (net (code "73") (name "unconnected-(U3-~{RTS}-Pad32)") (class "Default")
      (node (ref "U3") (pin "32") (pinfunction "~{RTS}_32") (pintype "output+no_connect"))
    )
  )
)
